# Peripherals.net
KiCad netlist of a schematic drawn in Altium Designer
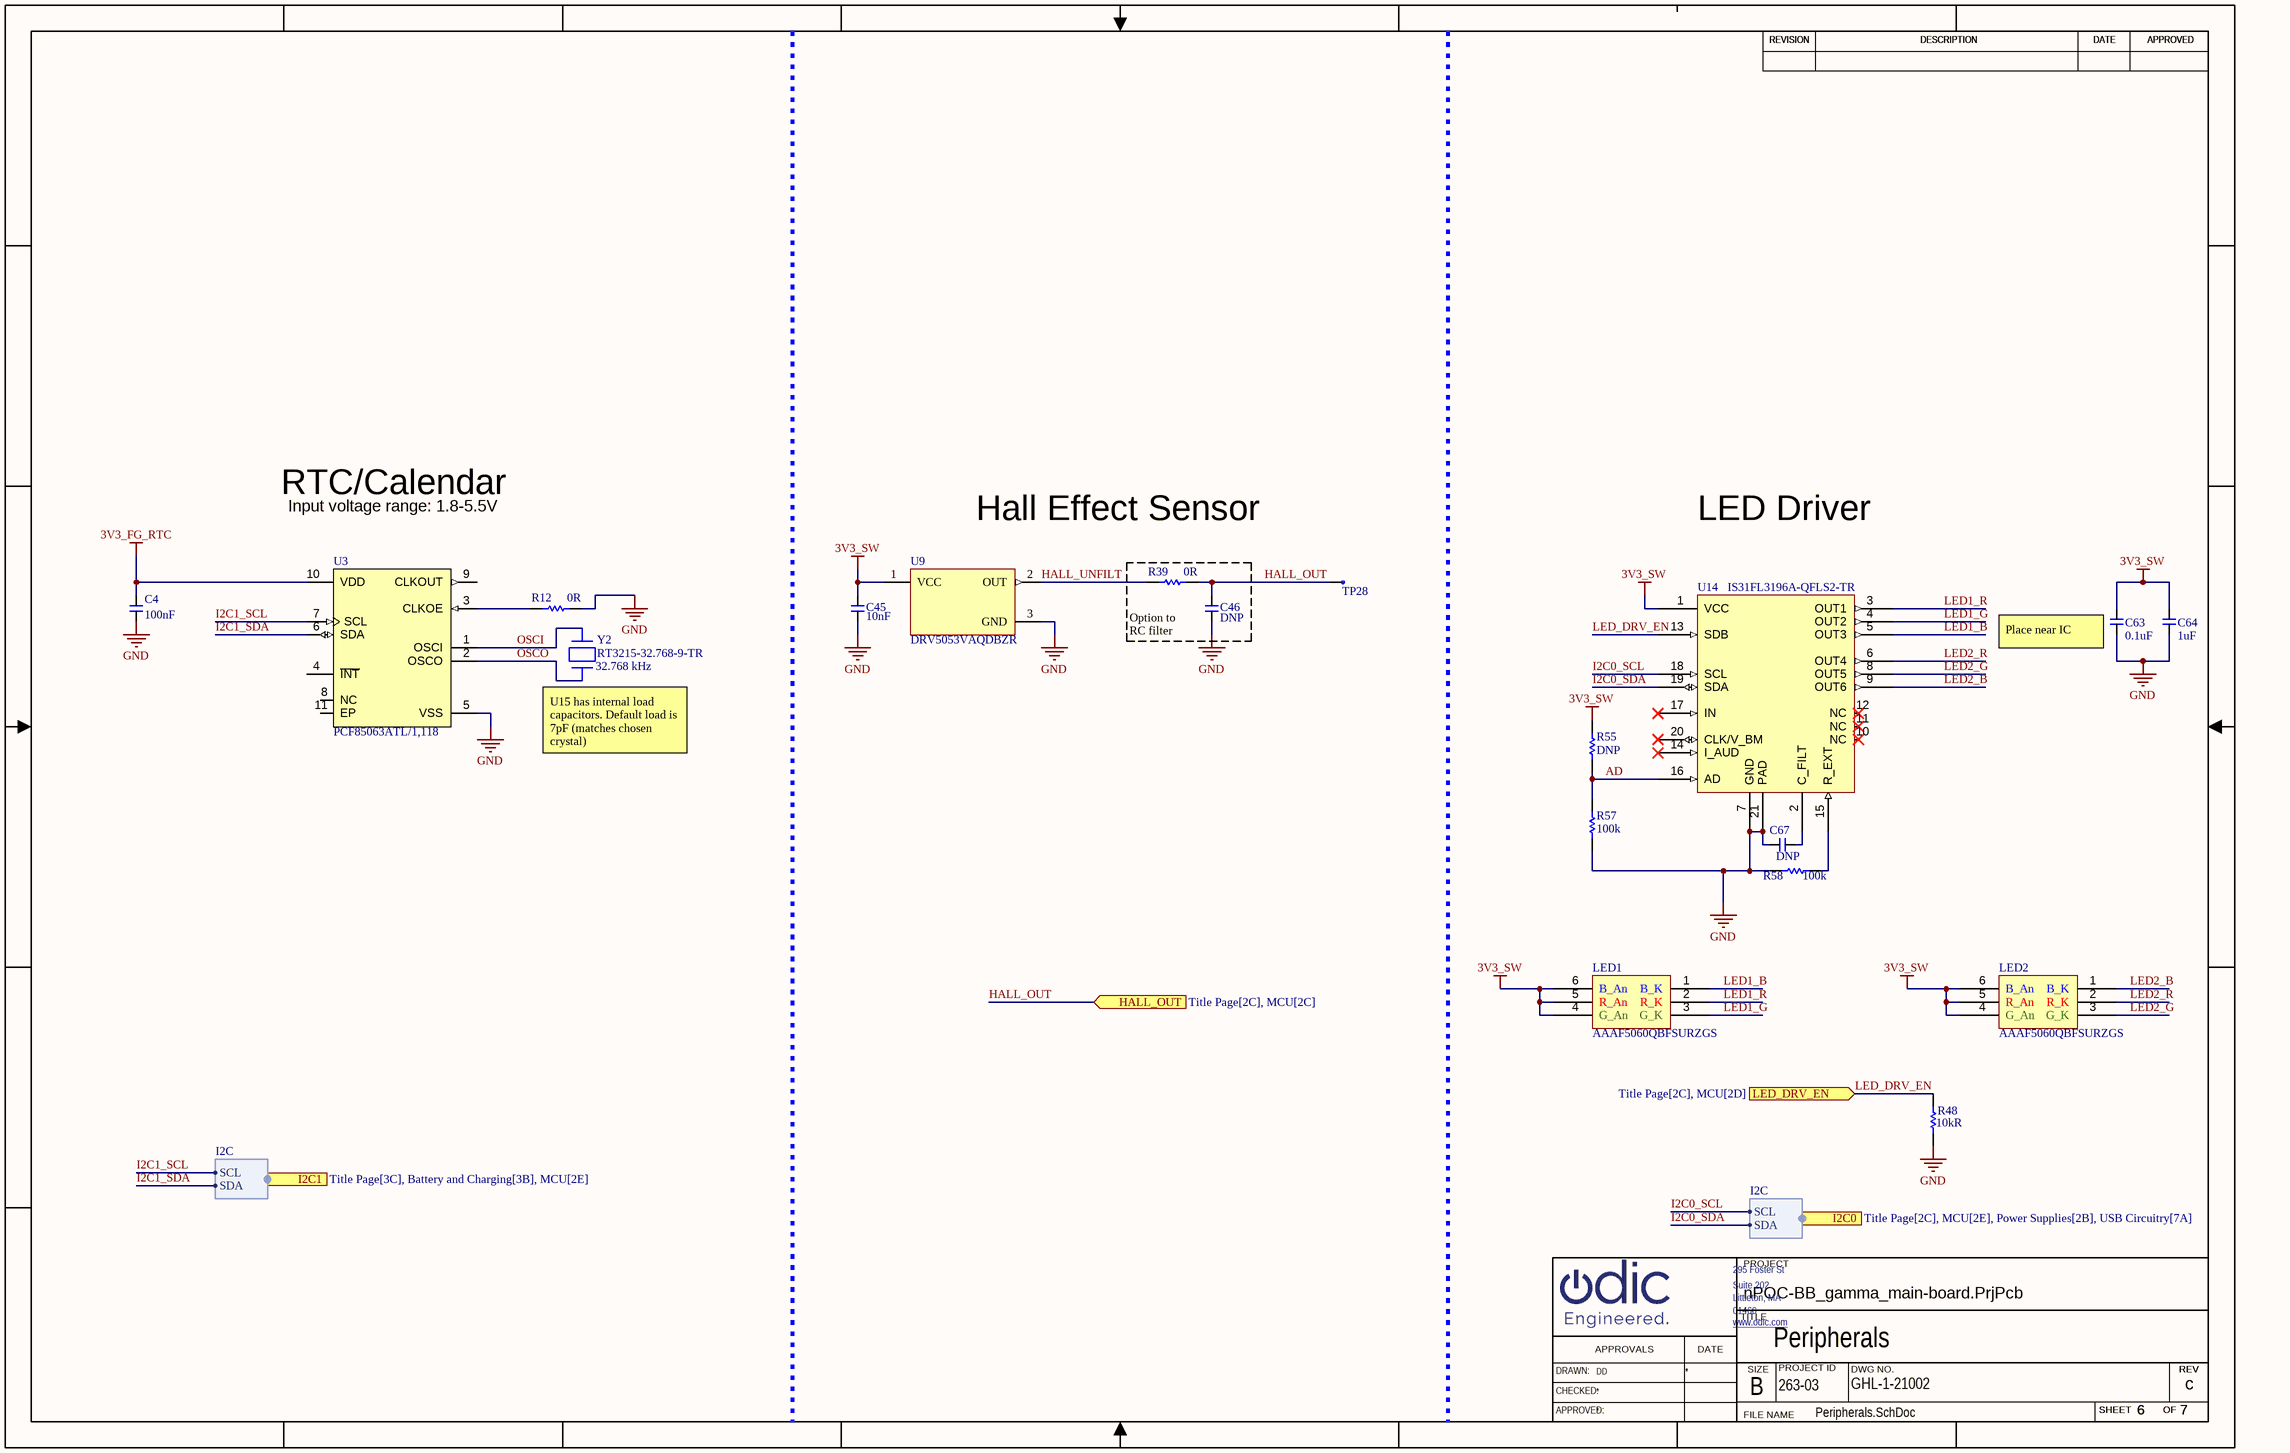
[diagram p0: Peripherals.SchDoc]

(export (version "E")
  (design (tool "Eeschema 10.0.6"))
  (components
    (comp (ref "C4")
      (value "C0402_100n_16V_10pct")
      (footprint "C0402")
      (description "0.1 µF ±10% 16V Ceramic Capacitor X7R 0402 (1005 Metric)")
      (fields
        (field (name "VOLTAGE") "16V")
        (field (name "TOLERANCE") "10%")
        (field (name "CAPACITANCE") "100nF")
      )
      (libsource (lib "Odic Inc") (part "cAP"))
    )
    (comp (ref "C45")
      (value "C0402_10n_6V3_10pct")
      (footprint "C0402")
      (description "CAP CER 10000PF 25V 10% X7R 0402")
      (fields
        (field (name "TOLERANCE") "10%")
        (field (name "CAPACITANCE") "10nF")
        (field (name "VOLTAGE") "25V")
      )
      (libsource (lib "Odic Inc") (part "cAP"))
    )
    (comp (ref "C46")
      (value "C0402 Footprint")
      (footprint "C0402")
      (description "Blank pads for future cap placements")
      (fields (field (name "INSTALL") "DNP"))
      (libsource (lib "Odic Inc") (part "cAP"))
    )
    (comp (ref "C63")
      (value "0.1uF")
      (footprint "C0402")
      (description "Cap Ceramic 0.1uF 25V X5R 10% Pad SMD 0402 Multi Layer Ceramic Capacitor (MLCC)")
      (fields (field (name "VOLTAGE") "25V") (field (name "TOLERANCE") "10%"))
      (libsource (lib "Odic Inc") (part "cAP"))
    )
    (comp (ref "C64")
      (value "1uF")
      (footprint "C0402")
      (description "CAP CER 1UF 16V X5R 0402")
      (fields (field (name "VOLTAGE") "16V") (field (name "TOLERANCE") "10%"))
      (libsource (lib "Odic Inc") (part "cAP"))
    )
    (comp (ref "C67")
      (value "N/A")
      (footprint "C0603")
      (description "DNP CAP")
      (fields
        (field (name "MANUFACTURER") "Samsung")
        (field (name "MANUFACTURER PART NUMBER") "CL10B104KB8NNWC")
        (field (name "INSTALL") "DNP")
      )
      (libsource (lib "Odic Inc") (part "cAP"))
    )
    (comp (ref "LED1")
      (value "AAAF5060QBFSURZGS")
      (footprint "led6_smt_5x6mm")
      (description "Blue/Red/Green 100º 400/800/1000 mcd Clear Surface Mount LED Lamp")
      (libsource (lib "Odic Inc") (part "AAAF5060QBFSURZGS-Symbol-1"))
    )
    (comp (ref "LED2")
      (value "AAAF5060QBFSURZGS")
      (footprint "led6_smt_5x6mm")
      (description "Blue/Red/Green 100º 400/800/1000 mcd Clear Surface Mount LED Lamp")
      (libsource (lib "Odic Inc") (part "AAAF5060QBFSURZGS-Symbol-1"))
    )
    (comp (ref "R12")
      (value "R0402_0R")
      (footprint "R0402")
      (description "RES 0 OHM JUMPER 1/16W 0402")
      (fields (field (name "RESISTANCE") "0R"))
      (libsource (lib "Odic Inc") (part "RES"))
    )
    (comp (ref "R39")
      (value "R0402_0R")
      (footprint "R0402")
      (description "RES 0 OHM JUMPER 1/16W 0402")
      (fields (field (name "RESISTANCE") "0R"))
      (libsource (lib "Odic Inc") (part "RES"))
    )
    (comp (ref "R48")
      (value "R0402_10k_1pct")
      (footprint "R0402")
      (description "Res Thick Film 0402 10K Ohm 1% 1/16W ±100ppm/°C Molded SMD SMD T/R")
      (fields (field (name "RESISTANCE") "10kR") (field (name "TOLERANCE") "1%"))
      (libsource (lib "Odic Inc") (part "RES"))
    )
    (comp (ref "R55")
      (value "DNP")
      (footprint "R0402")
      (description "Unpopulated 0402 pads. No part number associated with this \"component\"")
      (libsource (lib "Odic Inc") (part "RES"))
    )
    (comp (ref "R57")
      (value "100k")
      (footprint "R0402")
      (description "Res General Purpose Thick Film 0402 100K Ohm 1% 1/16W ±100ppm/°C Molded SMD Paper T/R")
      (fields (field (name "TOLERANCE") "1%"))
      (libsource (lib "Odic Inc") (part "RES"))
    )
    (comp (ref "R58")
      (value "100k")
      (footprint "R0402")
      (description "Res General Purpose Thick Film 0402 100K Ohm 1% 1/16W ±100ppm/°C Molded SMD Paper T/R")
      (fields (field (name "TOLERANCE") "1%"))
      (libsource (lib "Odic Inc") (part "RES"))
    )
    (comp (ref "TP28")
      (value "TPC30")
      (footprint "tpc30")
      (description "Test Point Circle 30")
      (libsource (lib "Odic Inc") (part "TPC"))
    )
    (comp (ref "U3")
      (value "PCF85063ATL/1,118")
      (footprint "dfn10_2p6x2p6_p5mm")
      (description "IC RTC CLK/CALENDAR I2C 10-SON")
      (libsource (lib "Odic Inc") (part "PCF85063A"))
    )
    (comp (ref "U9")
      (value "DRV5053VAQDBZR")
      (footprint "SOT23")
      (description "SENSOR HALL ANALOG SOT23-3 / Hall Effect Sensor Single Axis SOT-23-3")
      (libsource (lib "Odic Inc") (part "DRV5053VAQDBZR-symbol"))
    )
    (comp (ref "U14")
      (value "IS31FL3196A-QFLS2-TR")
      (footprint "qfn20_3x3_p4mm")
      (description "6-Channel Light Effect LED Driver with I2C Interface 2.7V to 5.5V Input 20-Pin QFN T/R")
      (libsource (lib "Odic Inc") (part "IS31FL3196A-QFLS2-TR-Symbol-1"))
    )
    (comp (ref "Y2")
      (value "RT3215-32.768-9-TR")
      (footprint "xtal2_3p2x1p5")
      (description "RT3215 Series 0.032768 ±20 ppm 9pF -40°C TO +85°C SMT Tuning Fork Crystal")
      (fields (field (name "OPERATING FREQUENCY") "32.768 kHz"))
      (libsource (lib "Odic Inc") (part "Y*"))
    )
  )
  (nets
    (net (code "2") (name "/AD") (class "Default")
      (node (ref "R55") (pin "1") (pinfunction "1_1") (pintype "passive"))
      (node (ref "R57") (pin "2") (pinfunction "2_2") (pintype "passive"))
      (node (ref "U14") (pin "16") (pinfunction "AD_16") (pintype "input"))
    )
    (net (code "3") (name "/HALL_OUT") (class "Default")
      (node (ref "C46") (pin "2") (pinfunction "2_2") (pintype "passive"))
      (node (ref "R39") (pin "2") (pinfunction "2_2") (pintype "passive"))
      (node (ref "TP28") (pin "1") (pinfunction "1_1") (pintype "passive"))
    )
    (net (code "4") (name "/HALL_UNFILT") (class "Default")
      (node (ref "R39") (pin "1") (pinfunction "1_1") (pintype "passive"))
      (node (ref "U9") (pin "2") (pinfunction "OUT_2") (pintype "output"))
    )
    (net (code "5") (name "/I2C0_SCL") (class "Default")
      (node (ref "U14") (pin "18") (pinfunction "SCL_18") (pintype "input"))
    )
    (net (code "6") (name "/I2C0_SDA") (class "Default")
      (node (ref "U14") (pin "19") (pinfunction "SDA_19") (pintype "bidirectional"))
    )
    (net (code "7") (name "/I2C1_SCL") (class "Default")
      (node (ref "U3") (pin "7") (pinfunction "SCL_7") (pintype "input"))
    )
    (net (code "8") (name "/I2C1_SDA") (class "Default")
      (node (ref "U3") (pin "6") (pinfunction "SDA_6") (pintype "bidirectional"))
    )
    (net (code "9") (name "/LED1_B") (class "Default")
      (node (ref "LED1") (pin "1") (pinfunction "B_K_1") (pintype "passive"))
      (node (ref "U14") (pin "5") (pinfunction "OUT3_5") (pintype "output"))
    )
    (net (code "10") (name "/LED1_G") (class "Default")
      (node (ref "LED1") (pin "3") (pinfunction "G_K_3") (pintype "passive"))
      (node (ref "U14") (pin "4") (pinfunction "OUT2_4") (pintype "output"))
    )
    (net (code "11") (name "/LED1_R") (class "Default")
      (node (ref "LED1") (pin "2") (pinfunction "R_K_2") (pintype "passive"))
      (node (ref "U14") (pin "3") (pinfunction "OUT1_3") (pintype "output"))
    )
    (net (code "12") (name "/LED2_B") (class "Default")
      (node (ref "LED2") (pin "1") (pinfunction "B_K_1") (pintype "passive"))
      (node (ref "U14") (pin "9") (pinfunction "OUT6_9") (pintype "output"))
    )
    (net (code "13") (name "/LED2_G") (class "Default")
      (node (ref "LED2") (pin "3") (pinfunction "G_K_3") (pintype "passive"))
      (node (ref "U14") (pin "8") (pinfunction "OUT5_8") (pintype "output"))
    )
    (net (code "14") (name "/LED2_R") (class "Default")
      (node (ref "LED2") (pin "2") (pinfunction "R_K_2") (pintype "passive"))
      (node (ref "U14") (pin "6") (pinfunction "OUT4_6") (pintype "output"))
    )
    (net (code "15") (name "/LED_DRV_EN") (class "Default")
      (node (ref "R48") (pin "1") (pinfunction "1_1") (pintype "passive"))
      (node (ref "U14") (pin "13") (pinfunction "SDB_13") (pintype "input"))
    )
    (net (code "16") (name "/OSCI") (class "Default")
      (node (ref "U3") (pin "1") (pinfunction "OSCI_1") (pintype "passive"))
      (node (ref "Y2") (pin "1") (pinfunction "1_1") (pintype "passive"))
    )
    (net (code "17") (name "/OSCO") (class "Default")
      (node (ref "U3") (pin "2") (pinfunction "OSCO_2") (pintype "passive"))
      (node (ref "Y2") (pin "2") (pinfunction "2_2") (pintype "passive"))
    )
    (net (code "19") (name "3V3_FG_RTC") (class "Default")
      (node (ref "C4") (pin "1") (pinfunction "1_1") (pintype "passive"))
      (node (ref "U3") (pin "10") (pinfunction "VDD_10") (pintype "power_in"))
    )
    (net (code "20") (name "3V3_SW") (class "Default")
      (node (ref "C45") (pin "2") (pinfunction "2_2") (pintype "passive"))
      (node (ref "C63") (pin "2") (pinfunction "2_2") (pintype "passive"))
      (node (ref "C64") (pin "2") (pinfunction "2_2") (pintype "passive"))
      (node (ref "LED1") (pin "4") (pinfunction "G_An_4") (pintype "passive"))
      (node (ref "LED1") (pin "5") (pinfunction "R_An_5") (pintype "passive"))
      (node (ref "LED1") (pin "6") (pinfunction "B_An_6") (pintype "passive"))
      (node (ref "LED2") (pin "4") (pinfunction "G_An_4") (pintype "passive"))
      (node (ref "LED2") (pin "5") (pinfunction "R_An_5") (pintype "passive"))
      (node (ref "LED2") (pin "6") (pinfunction "B_An_6") (pintype "passive"))
      (node (ref "R55") (pin "2") (pinfunction "2_2") (pintype "passive"))
      (node (ref "U14") (pin "1") (pinfunction "VCC_1") (pintype "power_in"))
      (node (ref "U9") (pin "1") (pinfunction "VCC_1") (pintype "power_in"))
    )
    (net (code "21") (name "GND") (class "Default")
      (node (ref "C4") (pin "2") (pinfunction "2_2") (pintype "passive"))
      (node (ref "C45") (pin "1") (pinfunction "1_1") (pintype "passive"))
      (node (ref "C46") (pin "1") (pinfunction "1_1") (pintype "passive"))
      (node (ref "C63") (pin "1") (pinfunction "1_1") (pintype "passive"))
      (node (ref "C64") (pin "1") (pinfunction "1_1") (pintype "passive"))
      (node (ref "C67") (pin "2") (pinfunction "2_2") (pintype "passive"))
      (node (ref "R12") (pin "2") (pinfunction "2_2") (pintype "passive"))
      (node (ref "R48") (pin "2") (pinfunction "2_2") (pintype "passive"))
      (node (ref "R57") (pin "1") (pinfunction "1_1") (pintype "passive"))
      (node (ref "R58") (pin "2") (pinfunction "2_2") (pintype "passive"))
      (node (ref "U14") (pin "21") (pinfunction "PAD_21") (pintype "passive"))
      (node (ref "U14") (pin "7") (pinfunction "GND_7") (pintype "passive"))
      (node (ref "U3") (pin "5") (pinfunction "VSS_5") (pintype "power_in"))
      (node (ref "U9") (pin "3") (pinfunction "GND_3") (pintype "power_in"))
    )
    (net (code "22") (name "Net-(U3-CLKOE)") (class "Default")
      (node (ref "R12") (pin "1") (pinfunction "1_1") (pintype "passive"))
      (node (ref "U3") (pin "3") (pinfunction "CLKOE_3") (pintype "input"))
    )
    (net (code "23") (name "Net-(U14-C_FILT)") (class "Default")
      (node (ref "C67") (pin "1") (pinfunction "1_1") (pintype "passive"))
      (node (ref "U14") (pin "2") (pinfunction "C_FILT_2") (pintype "passive"))
    )
    (net (code "24") (name "Net-(U14-R_EXT)") (class "Default")
      (node (ref "R58") (pin "1") (pinfunction "1_1") (pintype "passive"))
      (node (ref "U14") (pin "15") (pinfunction "R_EXT_15") (pintype "input"))
    )
    (net (code "25") (name "unconnected-(U3-CLKOUT-Pad9)") (class "Default")
      (node (ref "U3") (pin "9") (pinfunction "CLKOUT_9") (pintype "output"))
    )
    (net (code "26") (name "unconnected-(U3-EP-Pad11)") (class "Default")
      (node (ref "U3") (pin "11") (pinfunction "EP_11") (pintype "power_in"))
    )
    (net (code "27") (name "unconnected-(U3-NC-Pad8)") (class "Default")
      (node (ref "U3") (pin "8") (pinfunction "NC_8") (pintype "passive"))
    )
    (net (code "28") (name "unconnected-(U3-~{INT}-Pad4)") (class "Default")
      (node (ref "U3") (pin "4") (pinfunction "~{INT}_4") (pintype "open_collector"))
    )
    (net (code "29") (name "unconnected-(U14-CLK{slash}V_BM-Pad20)") (class "Default")
      (node (ref "U14") (pin "20") (pinfunction "CLK/V_BM_20") (pintype "bidirectional+no_connect"))
    )
    (net (code "30") (name "unconnected-(U14-IN-Pad17)") (class "Default")
      (node (ref "U14") (pin "17") (pinfunction "IN_17") (pintype "input+no_connect"))
    )
    (net (code "31") (name "unconnected-(U14-I_AUD-Pad14)") (class "Default")
      (node (ref "U14") (pin "14") (pinfunction "I_AUD_14") (pintype "input+no_connect"))
    )
    (net (code "32") (name "unconnected-(U14-NC-Pad10)") (class "Default")
      (node (ref "U14") (pin "10") (pinfunction "NC_10") (pintype "passive+no_connect"))
    )
    (net (code "33") (name "unconnected-(U14-NC-Pad11)") (class "Default")
      (node (ref "U14") (pin "11") (pinfunction "NC_11") (pintype "passive+no_connect"))
    )
    (net (code "34") (name "unconnected-(U14-NC-Pad12)") (class "Default")
      (node (ref "U14") (pin "12") (pinfunction "NC_12") (pintype "passive+no_connect"))
    )
  )
)
